# MCU.net
KiCad netlist of a schematic drawn in Altium Designer
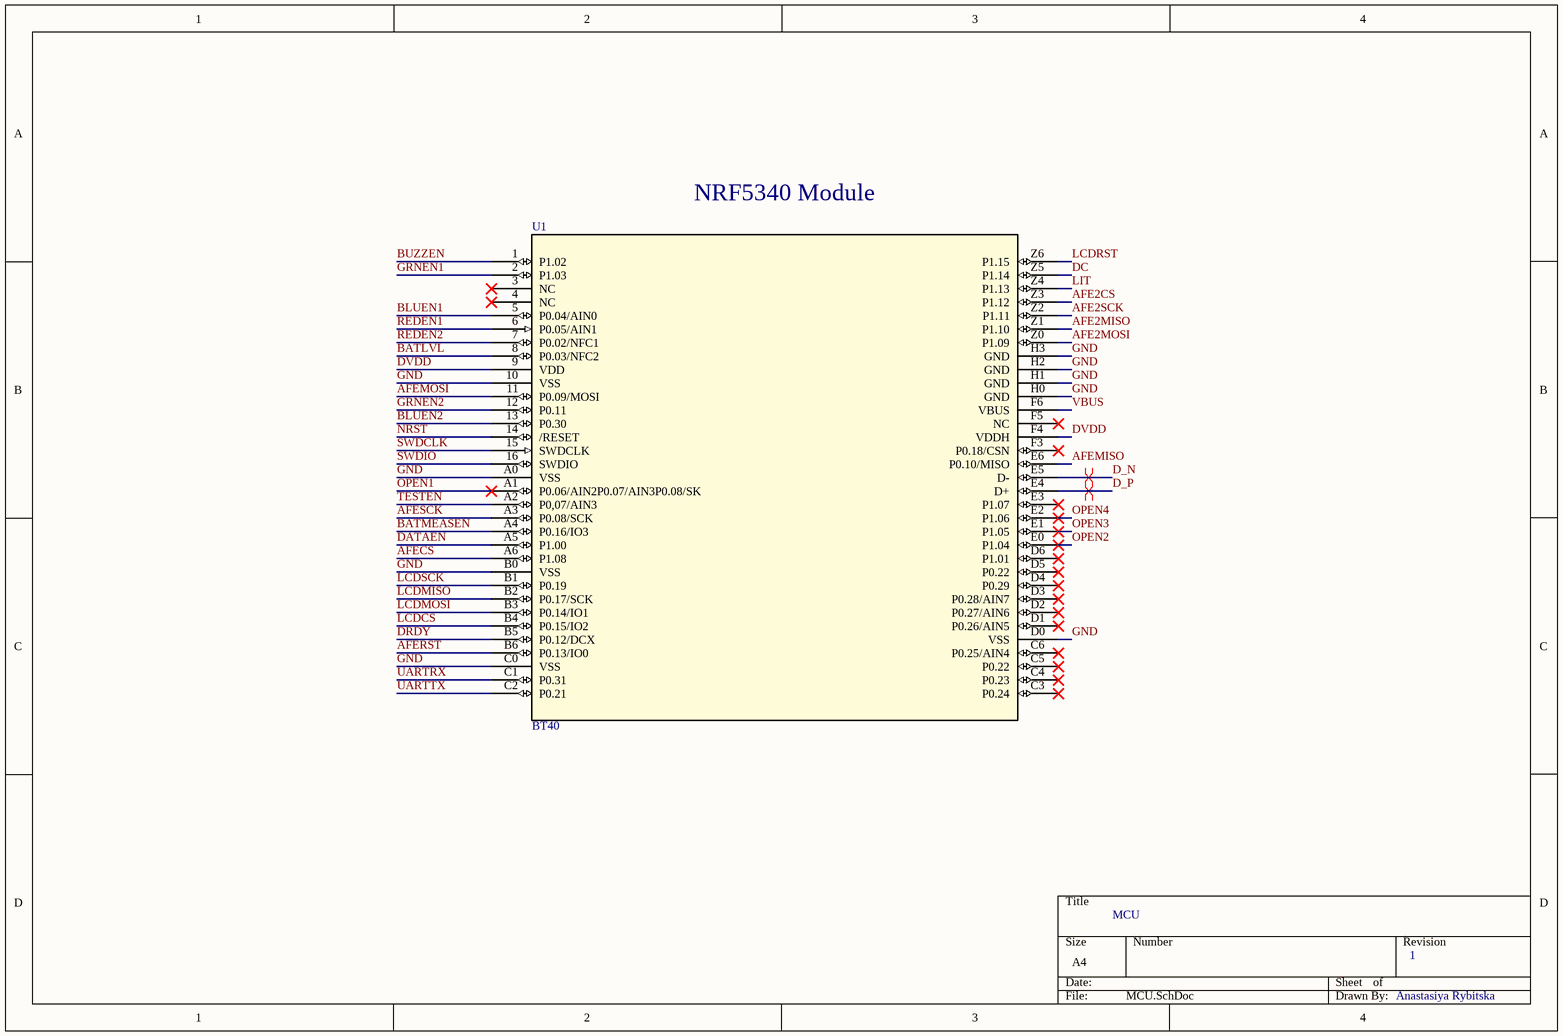
[diagram p0: MCU.SchDoc]

(export (version "E")
  (design (tool "Eeschema 10.0.6"))
  (components
    (comp (ref "U1")
      (value "BT40")
      (footprint "BT40E_FAN_FNL")
      (description "No Description Available")
      (fields (field (name "COPYRIGHT") "Copyright (C) 2023 Ultra Librarian. All rights reserved."))
      (libsource (lib "Schlib1") (part "BT40"))
    )
  )
  (nets
    (net (code "1") (name "/AFE2CS") (class "Default")
      (node (ref "U1") (pin "Z3") (pinfunction "P1.12_Z3") (pintype "bidirectional"))
    )
    (net (code "2") (name "/AFE2MISO") (class "Default")
      (node (ref "U1") (pin "Z1") (pinfunction "P1.10_Z1") (pintype "bidirectional"))
    )
    (net (code "3") (name "/AFE2MOSI") (class "Default")
      (node (ref "U1") (pin "Z0") (pinfunction "P1.09_Z0") (pintype "bidirectional"))
    )
    (net (code "4") (name "/AFE2SCK") (class "Default")
      (node (ref "U1") (pin "Z2") (pinfunction "P1.11_Z2") (pintype "bidirectional"))
    )
    (net (code "5") (name "/AFECS") (class "Default")
      (node (ref "U1") (pin "A6") (pinfunction "P1.08_A6") (pintype "bidirectional"))
    )
    (net (code "6") (name "/AFEMISO") (class "Default")
      (node (ref "U1") (pin "E6") (pinfunction "P0.10/MISO_E6") (pintype "bidirectional"))
    )
    (net (code "7") (name "/AFEMOSI") (class "Default")
      (node (ref "U1") (pin "11") (pinfunction "P0.09/MOSI_11") (pintype "bidirectional"))
    )
    (net (code "8") (name "/AFERST") (class "Default")
      (node (ref "U1") (pin "B6") (pinfunction "P0.13/IO0_B6") (pintype "bidirectional"))
    )
    (net (code "9") (name "/AFESCK") (class "Default")
      (node (ref "U1") (pin "A3") (pinfunction "P0.08/SCK_A3") (pintype "bidirectional"))
    )
    (net (code "10") (name "/BATLVL") (class "Default")
      (node (ref "U1") (pin "8") (pinfunction "P0.03/NFC2_8") (pintype "bidirectional"))
    )
    (net (code "11") (name "/BATMEASEN") (class "Default")
      (node (ref "U1") (pin "A4") (pinfunction "P0.16/IO3_A4") (pintype "bidirectional"))
    )
    (net (code "12") (name "/BLUEN1") (class "Default")
      (node (ref "U1") (pin "5") (pinfunction "P0.04/AIN0_5") (pintype "bidirectional"))
    )
    (net (code "13") (name "/BLUEN2") (class "Default")
      (node (ref "U1") (pin "13") (pinfunction "P0.30_13") (pintype "bidirectional"))
    )
    (net (code "14") (name "/BUZZEN") (class "Default")
      (node (ref "U1") (pin "1") (pinfunction "P1.02_1") (pintype "bidirectional"))
    )
    (net (code "15") (name "/DATAEN") (class "Default")
      (node (ref "U1") (pin "A5") (pinfunction "P1.00_A5") (pintype "bidirectional"))
    )
    (net (code "16") (name "/DC") (class "Default")
      (node (ref "U1") (pin "Z5") (pinfunction "P1.14_Z5") (pintype "bidirectional"))
    )
    (net (code "17") (name "/DRDY") (class "Default")
      (node (ref "U1") (pin "B5") (pinfunction "P0.12/DCX_B5") (pintype "bidirectional"))
    )
    (net (code "18") (name "/DVDD") (class "Default")
      (node (ref "U1") (pin "9") (pinfunction "VDD_9") (pintype "power_in"))
      (node (ref "U1") (pin "F4") (pinfunction "VDDH_F4") (pintype "power_in"))
    )
    (net (code "19") (name "/D_N") (class "Default")
      (node (ref "U1") (pin "E5") (pinfunction "D-_E5") (pintype "bidirectional"))
    )
    (net (code "20") (name "/D_P") (class "Default")
      (node (ref "U1") (pin "E4") (pinfunction "D+_E4") (pintype "bidirectional"))
    )
    (net (code "21") (name "/GND") (class "Default")
      (node (ref "U1") (pin "10") (pinfunction "VSS_10") (pintype "power_in"))
      (node (ref "U1") (pin "A0") (pinfunction "VSS_A0") (pintype "power_in"))
      (node (ref "U1") (pin "B0") (pinfunction "VSS_B0") (pintype "power_in"))
      (node (ref "U1") (pin "C0") (pinfunction "VSS_C0") (pintype "power_in"))
      (node (ref "U1") (pin "D0") (pinfunction "VSS_D0") (pintype "power_in"))
      (node (ref "U1") (pin "H0") (pinfunction "GND_H0") (pintype "power_in"))
      (node (ref "U1") (pin "H1") (pinfunction "GND_H1") (pintype "power_in"))
      (node (ref "U1") (pin "H2") (pinfunction "GND_H2") (pintype "power_in"))
      (node (ref "U1") (pin "H3") (pinfunction "GND_H3") (pintype "power_in"))
    )
    (net (code "22") (name "/GRNEN1") (class "Default")
      (node (ref "U1") (pin "2") (pinfunction "P1.03_2") (pintype "bidirectional"))
    )
    (net (code "23") (name "/GRNEN2") (class "Default")
      (node (ref "U1") (pin "12") (pinfunction "P0.11_12") (pintype "bidirectional"))
    )
    (net (code "24") (name "/LCDCS") (class "Default")
      (node (ref "U1") (pin "B4") (pinfunction "P0.15/IO2_B4") (pintype "bidirectional"))
    )
    (net (code "25") (name "/LCDMISO") (class "Default")
      (node (ref "U1") (pin "B2") (pinfunction "P0.17/SCK_B2") (pintype "bidirectional"))
    )
    (net (code "26") (name "/LCDMOSI") (class "Default")
      (node (ref "U1") (pin "B3") (pinfunction "P0.14/IO1_B3") (pintype "bidirectional"))
    )
    (net (code "27") (name "/LCDRST") (class "Default")
      (node (ref "U1") (pin "Z6") (pinfunction "P1.15_Z6") (pintype "bidirectional"))
    )
    (net (code "28") (name "/LCDSCK") (class "Default")
      (node (ref "U1") (pin "B1") (pinfunction "P0.19_B1") (pintype "bidirectional"))
    )
    (net (code "29") (name "/LIT") (class "Default")
      (node (ref "U1") (pin "Z4") (pinfunction "P1.13_Z4") (pintype "bidirectional"))
    )
    (net (code "30") (name "/NRST") (class "Default")
      (node (ref "U1") (pin "14") (pinfunction "/RESET_14") (pintype "bidirectional"))
    )
    (net (code "31") (name "/OPEN1") (class "Default")
      (node (ref "U1") (pin "A1") (pinfunction "P0.06/AIN2P0.07/AIN3P0.08/SK_A1") (pintype "bidirectional+no_connect"))
    )
    (net (code "32") (name "/OPEN2") (class "Default")
      (node (ref "U1") (pin "E0") (pinfunction "P1.04_E0") (pintype "bidirectional+no_connect"))
    )
    (net (code "33") (name "/OPEN3") (class "Default")
      (node (ref "U1") (pin "E1") (pinfunction "P1.05_E1") (pintype "bidirectional+no_connect"))
    )
    (net (code "34") (name "/OPEN4") (class "Default")
      (node (ref "U1") (pin "E2") (pinfunction "P1.06_E2") (pintype "bidirectional+no_connect"))
    )
    (net (code "35") (name "/REDEN1") (class "Default")
      (node (ref "U1") (pin "6") (pinfunction "P0.05/AIN1_6") (pintype "input"))
    )
    (net (code "36") (name "/REDEN2") (class "Default")
      (node (ref "U1") (pin "7") (pinfunction "P0.02/NFC1_7") (pintype "bidirectional"))
    )
    (net (code "37") (name "/SWDCLK") (class "Default")
      (node (ref "U1") (pin "15") (pinfunction "SWDCLK_15") (pintype "input"))
    )
    (net (code "38") (name "/SWDIO") (class "Default")
      (node (ref "U1") (pin "16") (pinfunction "SWDIO_16") (pintype "bidirectional"))
    )
    (net (code "39") (name "/TESTEN") (class "Default")
      (node (ref "U1") (pin "A2") (pinfunction "P0,07/AIN3_A2") (pintype "bidirectional"))
    )
    (net (code "40") (name "/UARTRX") (class "Default")
      (node (ref "U1") (pin "C1") (pinfunction "P0.31_C1") (pintype "bidirectional"))
    )
    (net (code "41") (name "/UARTTX") (class "Default")
      (node (ref "U1") (pin "C2") (pinfunction "P0.21_C2") (pintype "bidirectional"))
    )
    (net (code "42") (name "/VBUS") (class "Default")
      (node (ref "U1") (pin "F6") (pinfunction "VBUS_F6") (pintype "power_in"))
    )
    (net (code "43") (name "unconnected-(U1-NC-Pad3)") (class "Default")
      (node (ref "U1") (pin "3") (pinfunction "NC_3") (pintype "passive+no_connect"))
    )
    (net (code "44") (name "unconnected-(U1-NC-Pad4)") (class "Default")
      (node (ref "U1") (pin "4") (pinfunction "NC_4") (pintype "passive+no_connect"))
    )
    (net (code "45") (name "unconnected-(U1-NC-PadF5)") (class "Default")
      (node (ref "U1") (pin "F5") (pinfunction "NC_F5") (pintype "passive+no_connect"))
    )
    (net (code "46") (name "unconnected-(U1-P0.18{slash}CSN-PadF3)") (class "Default")
      (node (ref "U1") (pin "F3") (pinfunction "P0.18/CSN_F3") (pintype "bidirectional+no_connect"))
    )
    (net (code "47") (name "unconnected-(U1-P0.22-PadC5)") (class "Default")
      (node (ref "U1") (pin "C5") (pinfunction "P0.22_C5") (pintype "bidirectional+no_connect"))
    )
    (net (code "48") (name "unconnected-(U1-P0.22-PadD5)") (class "Default")
      (node (ref "U1") (pin "D5") (pinfunction "P0.22_D5") (pintype "bidirectional+no_connect"))
    )
    (net (code "49") (name "unconnected-(U1-P0.23-PadC4)") (class "Default")
      (node (ref "U1") (pin "C4") (pinfunction "P0.23_C4") (pintype "bidirectional+no_connect"))
    )
    (net (code "50") (name "unconnected-(U1-P0.24-PadC3)") (class "Default")
      (node (ref "U1") (pin "C3") (pinfunction "P0.24_C3") (pintype "bidirectional+no_connect"))
    )
    (net (code "51") (name "unconnected-(U1-P0.25{slash}AIN4-PadC6)") (class "Default")
      (node (ref "U1") (pin "C6") (pinfunction "P0.25/AIN4_C6") (pintype "bidirectional+no_connect"))
    )
    (net (code "52") (name "unconnected-(U1-P0.26{slash}AIN5-PadD1)") (class "Default")
      (node (ref "U1") (pin "D1") (pinfunction "P0.26/AIN5_D1") (pintype "bidirectional+no_connect"))
    )
    (net (code "53") (name "unconnected-(U1-P0.27{slash}AIN6-PadD2)") (class "Default")
      (node (ref "U1") (pin "D2") (pinfunction "P0.27/AIN6_D2") (pintype "bidirectional+no_connect"))
    )
    (net (code "54") (name "unconnected-(U1-P0.28{slash}AIN7-PadD3)") (class "Default")
      (node (ref "U1") (pin "D3") (pinfunction "P0.28/AIN7_D3") (pintype "bidirectional+no_connect"))
    )
    (net (code "55") (name "unconnected-(U1-P0.29-PadD4)") (class "Default")
      (node (ref "U1") (pin "D4") (pinfunction "P0.29_D4") (pintype "bidirectional+no_connect"))
    )
    (net (code "56") (name "unconnected-(U1-P1.01-PadD6)") (class "Default")
      (node (ref "U1") (pin "D6") (pinfunction "P1.01_D6") (pintype "bidirectional+no_connect"))
    )
    (net (code "57") (name "unconnected-(U1-P1.07-PadE3)") (class "Default")
      (node (ref "U1") (pin "E3") (pinfunction "P1.07_E3") (pintype "bidirectional+no_connect"))
    )
  )
)
